# Tock.net
KiCad netlist of a schematic drawn in EAGLE
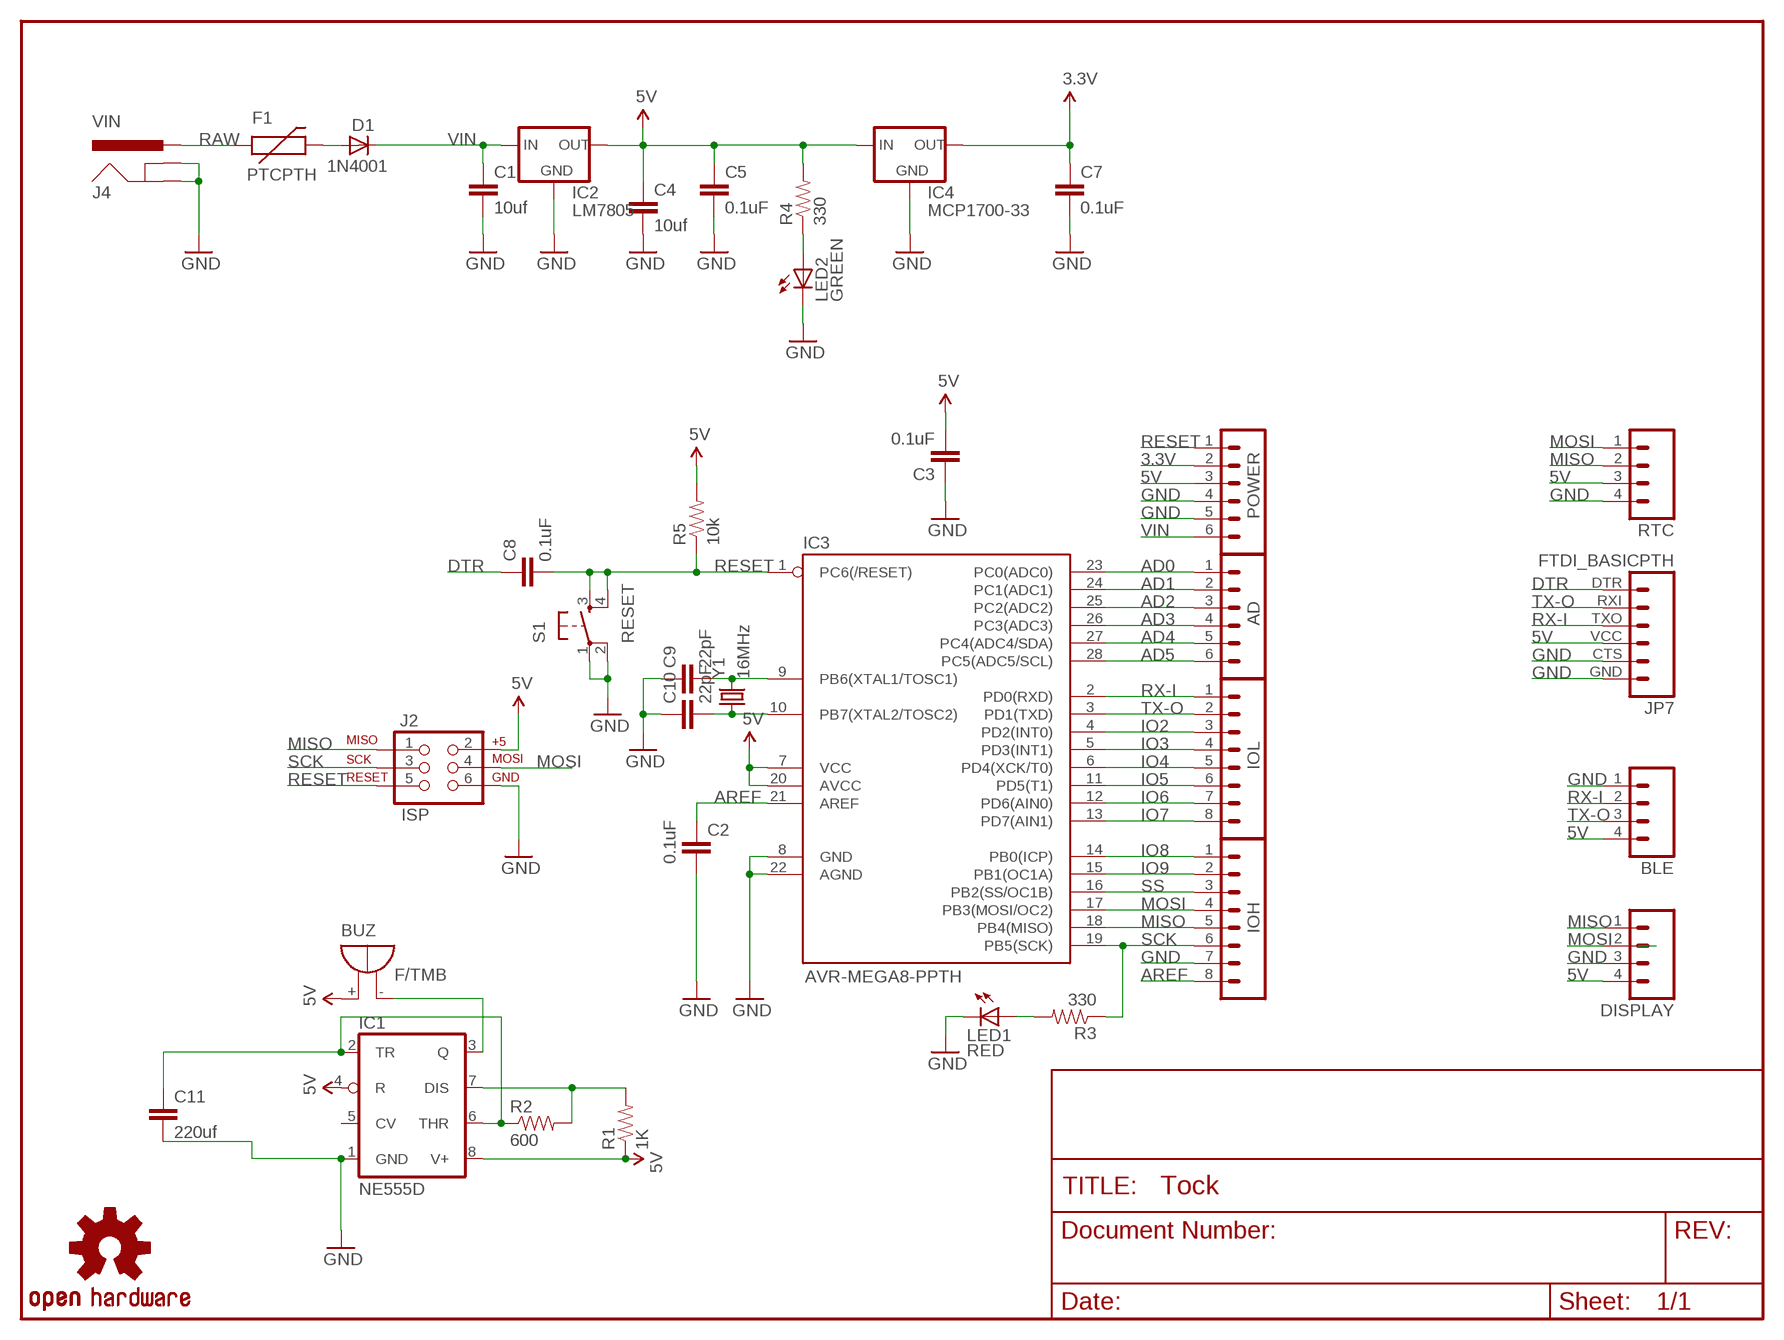
[diagram p0: schematic, sheet 1]

(export (version "E")
  (design (tool "Eeschema 10.0.6"))
  (components
    (comp (ref "AD")
      (value "M06LOCK")
      (footprint "eagle-import:1X06_LOCK")
      (libsource (lib "eagle-import") (part "M06LOCK"))
    )
    (comp (ref "BLE")
      (value "M04LOCK")
      (footprint "eagle-import:1X04_LOCK")
      (libsource (lib "eagle-import") (part "M04LOCK"))
    )
    (comp (ref "BUZ")
      (value "F/TMB")
      (footprint "eagle-import:F_TMB")
      (libsource (lib "eagle-import") (part "F/TMB"))
    )
    (comp (ref "C1")
      (value "10uf")
      (footprint "eagle-import:0805")
      (libsource (lib "eagle-import") (part "SparkFun-Passives_CAP0805"))
    )
    (comp (ref "C2")
      (value "0.1uF")
      (footprint "eagle-import:0805")
      (libsource (lib "eagle-import") (part "SparkFun-Passives_CAP0805"))
    )
    (comp (ref "C3")
      (value "0.1uF")
      (footprint "eagle-import:CAP-PTH-SMALL2")
      (libsource (lib "eagle-import") (part "CAPPTH2"))
    )
    (comp (ref "C4")
      (value "10uf")
      (footprint "eagle-import:0805")
      (libsource (lib "eagle-import") (part "SparkFun-Passives_CAP0805"))
    )
    (comp (ref "C5")
      (value "0.1uF")
      (footprint "eagle-import:0805")
      (libsource (lib "eagle-import") (part "SparkFun-Passives_CAP0805"))
    )
    (comp (ref "C7")
      (value "0.1uF")
      (footprint "eagle-import:0805")
      (libsource (lib "eagle-import") (part "SparkFun-Passives_CAP0805"))
    )
    (comp (ref "C8")
      (value "0.1uF")
      (footprint "eagle-import:0805")
      (libsource (lib "eagle-import") (part "SparkFun-Passives_CAP0805"))
    )
    (comp (ref "C9")
      (value "22pF")
      (footprint "eagle-import:0805")
      (libsource (lib "eagle-import") (part "SparkFun-Passives_CAP0805"))
    )
    (comp (ref "C10")
      (value "22pF")
      (footprint "eagle-import:0805")
      (libsource (lib "eagle-import") (part "SparkFun-Passives_CAP0805"))
    )
    (comp (ref "C11")
      (value "220uf")
      (footprint "eagle-import:0805")
      (libsource (lib "eagle-import") (part "SparkFun-Passives_CAP0805"))
    )
    (comp (ref "D1")
      (value "1N4001")
      (footprint "eagle-import:DIODE-1N4001")
      (libsource (lib "eagle-import") (part "DIODEPTH"))
    )
    (comp (ref "DISPLAY")
      (value "M04LOCK")
      (footprint "eagle-import:1X04_LOCK")
      (libsource (lib "eagle-import") (part "M04LOCK"))
    )
    (comp (ref "F1")
      (value "PTCPTH")
      (footprint "eagle-import:PTC")
      (libsource (lib "eagle-import") (part "PTCPTH"))
    )
    (comp (ref "IC1")
      (value "NE555D")
      (footprint "eagle-import:SO08")
      (libsource (lib "eagle-import") (part "555DNE"))
    )
    (comp (ref "IC2")
      (value "LM7805")
      (footprint "eagle-import:TO-220-ALT")
      (libsource (lib "eagle-import") (part "V_REG_78XX-TO-220"))
    )
    (comp (ref "IC3")
      (value "AVR-MEGA8-PPTH")
      (footprint "eagle-import:DIL28-3")
      (libsource (lib "eagle-import") (part "AVR-MEGA8-PPTH"))
    )
    (comp (ref "IC4")
      (value "MCP1700-33")
      (footprint "eagle-import:TO-92")
      (libsource (lib "eagle-import") (part "V_REG_78XXTO-92"))
    )
    (comp (ref "IOH")
      (value "M08LOCK")
      (footprint "eagle-import:1X08_LOCK")
      (libsource (lib "eagle-import") (part "M08LOCK"))
    )
    (comp (ref "IOL")
      (value "M08LOCK")
      (footprint "eagle-import:1X08_LOCK")
      (libsource (lib "eagle-import") (part "M08LOCK"))
    )
    (comp (ref "J2")
      (value "ISP")
      (footprint "eagle-import:2X3")
      (libsource (lib "eagle-import") (part "AVR_SPI_PRG_6PTH"))
    )
    (comp (ref "J4")
      (value "VIN")
      (footprint "eagle-import:POWER_JACK_PTH_LOCK")
      (libsource (lib "eagle-import") (part "POWER_JACKPTH_LOCK"))
    )
    (comp (ref "JP7")
      (value "FTDI_BASICPTH")
      (footprint "eagle-import:FTDI_BASIC")
      (libsource (lib "eagle-import") (part "FTDI_BASICPTH"))
    )
    (comp (ref "LED1")
      (value "RED")
      (footprint "eagle-import:CHIP-LED0805")
      (libsource (lib "eagle-import") (part "LEDCHIP-LED0805"))
    )
    (comp (ref "LED2")
      (value "GREEN")
      (footprint "eagle-import:CHIP-LED0805")
      (libsource (lib "eagle-import") (part "LEDCHIP-LED0805"))
    )
    (comp (ref "POWER")
      (value "M06LOCK")
      (footprint "eagle-import:1X06_LOCK")
      (libsource (lib "eagle-import") (part "M06LOCK"))
    )
    (comp (ref "R1")
      (value "1K")
      (footprint "eagle-import:0805")
      (libsource (lib "eagle-import") (part "RESISTOR0805-RES"))
    )
    (comp (ref "R2")
      (value "600")
      (footprint "eagle-import:0805")
      (libsource (lib "eagle-import") (part "RESISTOR0805-RES"))
    )
    (comp (ref "R3")
      (value "330")
      (footprint "eagle-import:0805")
      (libsource (lib "eagle-import") (part "RESISTOR0805-RES"))
    )
    (comp (ref "R4")
      (value "330")
      (footprint "eagle-import:0805")
      (libsource (lib "eagle-import") (part "RESISTOR0805-RES"))
    )
    (comp (ref "R5")
      (value "10k")
      (footprint "eagle-import:0805")
      (libsource (lib "eagle-import") (part "RESISTOR0805-RES"))
    )
    (comp (ref "RTC")
      (value "M04LOCK")
      (footprint "eagle-import:1X04_LOCK")
      (libsource (lib "eagle-import") (part "M04LOCK"))
    )
    (comp (ref "S1")
      (value "RESET")
      (footprint "eagle-import:TACTILE-PTH")
      (libsource (lib "eagle-import") (part "TAC_SWITCHPTH"))
    )
    (comp (ref "U$7")
      (value "OSHW-LOGOM")
      (footprint "eagle-import:OSHW-LOGO-M")
      (libsource (lib "eagle-import") (part "OSHW-LOGOM"))
    )
    (comp (ref "Y1")
      (value "16MHz")
      (footprint "eagle-import:HC49US")
      (libsource (lib "eagle-import") (part "CRYSTALHC49US"))
    )
  )
  (nets
    (net (code "1") (name "/AD0") (class "Default")
      (node (ref "AD") (pin "1") (pinfunction "1_1") (pintype "passive"))
      (node (ref "IC3") (pin "23") (pinfunction "PC0(ADC0)_23") (pintype "bidirectional"))
    )
    (net (code "2") (name "/AD1") (class "Default")
      (node (ref "AD") (pin "2") (pinfunction "2_2") (pintype "passive"))
      (node (ref "IC3") (pin "24") (pinfunction "PC1(ADC1)_24") (pintype "bidirectional"))
    )
    (net (code "3") (name "/AD2") (class "Default")
      (node (ref "AD") (pin "3") (pinfunction "3_3") (pintype "passive"))
      (node (ref "IC3") (pin "25") (pinfunction "PC2(ADC2)_25") (pintype "bidirectional"))
    )
    (net (code "4") (name "/AD3") (class "Default")
      (node (ref "AD") (pin "4") (pinfunction "4_4") (pintype "passive"))
      (node (ref "IC3") (pin "26") (pinfunction "PC3(ADC3)_26") (pintype "bidirectional"))
    )
    (net (code "5") (name "/AD4") (class "Default")
      (node (ref "AD") (pin "5") (pinfunction "5_5") (pintype "passive"))
      (node (ref "IC3") (pin "27") (pinfunction "PC4(ADC4/SDA)_27") (pintype "bidirectional"))
    )
    (net (code "6") (name "/AD5") (class "Default")
      (node (ref "AD") (pin "6") (pinfunction "6_6") (pintype "passive"))
      (node (ref "IC3") (pin "28") (pinfunction "PC5(ADC5/SCL)_28") (pintype "bidirectional"))
    )
    (net (code "7") (name "/AREF") (class "Default")
      (node (ref "C2") (pin "1") (pinfunction "1_1") (pintype "passive"))
      (node (ref "IC3") (pin "21") (pinfunction "AREF_21") (pintype "bidirectional"))
      (node (ref "IOH") (pin "8") (pinfunction "8_8") (pintype "passive"))
    )
    (net (code "8") (name "/DTR") (class "Default")
      (node (ref "C8") (pin "1") (pinfunction "1_1") (pintype "passive"))
      (node (ref "JP7") (pin "DTR") (pinfunction "1_DTR") (pintype "passive"))
    )
    (net (code "9") (name "/IO2") (class "Default")
      (node (ref "IC3") (pin "4") (pinfunction "PD2(INT0)_4") (pintype "bidirectional"))
      (node (ref "IOL") (pin "3") (pinfunction "3_3") (pintype "passive"))
    )
    (net (code "10") (name "/IO3") (class "Default")
      (node (ref "IC3") (pin "5") (pinfunction "PD3(INT1)_5") (pintype "bidirectional"))
      (node (ref "IOL") (pin "4") (pinfunction "4_4") (pintype "passive"))
    )
    (net (code "11") (name "/IO4") (class "Default")
      (node (ref "IC3") (pin "6") (pinfunction "PD4(XCK/T0)_6") (pintype "bidirectional"))
      (node (ref "IOL") (pin "5") (pinfunction "5_5") (pintype "passive"))
    )
    (net (code "12") (name "/IO5") (class "Default")
      (node (ref "IC3") (pin "11") (pinfunction "PD5(T1)_11") (pintype "bidirectional"))
      (node (ref "IOL") (pin "6") (pinfunction "6_6") (pintype "passive"))
    )
    (net (code "13") (name "/IO6") (class "Default")
      (node (ref "IC3") (pin "12") (pinfunction "PD6(AIN0)_12") (pintype "bidirectional"))
      (node (ref "IOL") (pin "7") (pinfunction "7_7") (pintype "passive"))
    )
    (net (code "14") (name "/IO7") (class "Default")
      (node (ref "IC3") (pin "13") (pinfunction "PD7(AIN1)_13") (pintype "bidirectional"))
      (node (ref "IOL") (pin "8") (pinfunction "8_8") (pintype "passive"))
    )
    (net (code "15") (name "/IO8") (class "Default")
      (node (ref "IC3") (pin "14") (pinfunction "PB0(ICP)_14") (pintype "bidirectional"))
      (node (ref "IOH") (pin "1") (pinfunction "1_1") (pintype "passive"))
    )
    (net (code "16") (name "/IO9") (class "Default")
      (node (ref "IC3") (pin "15") (pinfunction "PB1(OC1A)_15") (pintype "bidirectional"))
      (node (ref "IOH") (pin "2") (pinfunction "2_2") (pintype "passive"))
    )
    (net (code "17") (name "/MISO") (class "Default")
      (node (ref "DISPLAY") (pin "1") (pinfunction "1_1") (pintype "passive"))
      (node (ref "IC3") (pin "18") (pinfunction "PB4(MISO)_18") (pintype "bidirectional"))
      (node (ref "IOH") (pin "5") (pinfunction "5_5") (pintype "passive"))
      (node (ref "J2") (pin "1") (pinfunction "1_1") (pintype "passive"))
      (node (ref "RTC") (pin "2") (pinfunction "2_2") (pintype "passive"))
    )
    (net (code "18") (name "/MOSI") (class "Default")
      (node (ref "DISPLAY") (pin "2") (pinfunction "2_2") (pintype "passive"))
      (node (ref "IC3") (pin "17") (pinfunction "PB3(MOSI/OC2)_17") (pintype "bidirectional"))
      (node (ref "IOH") (pin "4") (pinfunction "4_4") (pintype "passive"))
      (node (ref "J2") (pin "4") (pinfunction "4_4") (pintype "passive"))
      (node (ref "RTC") (pin "1") (pinfunction "1_1") (pintype "passive"))
    )
    (net (code "19") (name "/RAW") (class "Default")
      (node (ref "F1") (pin "P$1") (pinfunction "1_P$1") (pintype "bidirectional"))
      (node (ref "J4") (pin "PWR") (pinfunction "PWR_PWR") (pintype "bidirectional"))
    )
    (net (code "20") (name "/RESET") (class "Default")
      (node (ref "C8") (pin "2") (pinfunction "2_2") (pintype "passive"))
      (node (ref "IC3") (pin "1") (pinfunction "PC6(/RESET)_1") (pintype "bidirectional"))
      (node (ref "J2") (pin "5") (pinfunction "5_5") (pintype "passive"))
      (node (ref "POWER") (pin "1") (pinfunction "1_1") (pintype "passive"))
      (node (ref "R5") (pin "1") (pinfunction "1_1") (pintype "passive"))
      (node (ref "S1") (pin "3") (pinfunction "3_3") (pintype "passive"))
      (node (ref "S1") (pin "4") (pinfunction "4_4") (pintype "passive"))
    )
    (net (code "21") (name "/RX-I") (class "Default")
      (node (ref "BLE") (pin "2") (pinfunction "2_2") (pintype "passive"))
      (node (ref "IC3") (pin "2") (pinfunction "PD0(RXD)_2") (pintype "bidirectional"))
      (node (ref "IOL") (pin "1") (pinfunction "1_1") (pintype "passive"))
      (node (ref "JP7") (pin "TXO") (pinfunction "3_TXO") (pintype "passive"))
    )
    (net (code "22") (name "/SCK") (class "Default")
      (node (ref "IC3") (pin "19") (pinfunction "PB5(SCK)_19") (pintype "bidirectional"))
      (node (ref "IOH") (pin "6") (pinfunction "6_6") (pintype "passive"))
      (node (ref "J2") (pin "3") (pinfunction "3_3") (pintype "passive"))
      (node (ref "R3") (pin "1") (pinfunction "1_1") (pintype "passive"))
    )
    (net (code "23") (name "/SS") (class "Default")
      (node (ref "IC3") (pin "16") (pinfunction "PB2(SS/OC1B)_16") (pintype "bidirectional"))
      (node (ref "IOH") (pin "3") (pinfunction "3_3") (pintype "passive"))
    )
    (net (code "24") (name "/TX-O") (class "Default")
      (node (ref "BLE") (pin "3") (pinfunction "3_3") (pintype "passive"))
      (node (ref "IC3") (pin "3") (pinfunction "PD1(TXD)_3") (pintype "bidirectional"))
      (node (ref "IOL") (pin "2") (pinfunction "2_2") (pintype "passive"))
      (node (ref "JP7") (pin "RXI") (pinfunction "2_RXI") (pintype "passive"))
    )
    (net (code "25") (name "/VIN") (class "Default")
      (node (ref "C1") (pin "1") (pinfunction "1_1") (pintype "passive"))
      (node (ref "D1") (pin "C") (pinfunction "C_C") (pintype "passive"))
      (node (ref "IC2") (pin "IN") (pinfunction "IN_IN") (pintype "input"))
      (node (ref "POWER") (pin "6") (pinfunction "6_6") (pintype "passive"))
    )
    (net (code "26") (name "3.3V") (class "Default")
      (node (ref "C7") (pin "1") (pinfunction "1_1") (pintype "passive"))
      (node (ref "IC4") (pin "3") (pinfunction "OUT_3") (pintype "output"))
      (node (ref "POWER") (pin "2") (pinfunction "2_2") (pintype "passive"))
    )
    (net (code "27") (name "5V") (class "Default")
      (node (ref "BLE") (pin "4") (pinfunction "4_4") (pintype "passive"))
      (node (ref "BUZ") (pin "+") (pinfunction "+_+") (pintype "passive"))
      (node (ref "C3") (pin "2") (pinfunction "2_2") (pintype "passive"))
      (node (ref "C4") (pin "1") (pinfunction "1_1") (pintype "passive"))
      (node (ref "C5") (pin "1") (pinfunction "1_1") (pintype "passive"))
      (node (ref "DISPLAY") (pin "4") (pinfunction "4_4") (pintype "passive"))
      (node (ref "IC1") (pin "4") (pinfunction "R_4") (pintype "input"))
      (node (ref "IC1") (pin "8") (pinfunction "V+_8") (pintype "power_in"))
      (node (ref "IC2") (pin "OUT") (pinfunction "OUT_OUT") (pintype "output"))
      (node (ref "IC3") (pin "20") (pinfunction "AVCC_20") (pintype "bidirectional"))
      (node (ref "IC3") (pin "7") (pinfunction "VCC_7") (pintype "bidirectional"))
      (node (ref "IC4") (pin "2") (pinfunction "IN_2") (pintype "input"))
      (node (ref "J2") (pin "2") (pinfunction "2_2") (pintype "passive"))
      (node (ref "JP7") (pin "VCC") (pinfunction "4_VCC") (pintype "passive"))
      (node (ref "POWER") (pin "3") (pinfunction "3_3") (pintype "passive"))
      (node (ref "R1") (pin "1") (pinfunction "1_1") (pintype "passive"))
      (node (ref "R4") (pin "2") (pinfunction "2_2") (pintype "passive"))
      (node (ref "R5") (pin "2") (pinfunction "2_2") (pintype "passive"))
      (node (ref "RTC") (pin "3") (pinfunction "3_3") (pintype "passive"))
    )
    (net (code "28") (name "GND") (class "Default")
      (node (ref "BLE") (pin "1") (pinfunction "1_1") (pintype "passive"))
      (node (ref "C1") (pin "2") (pinfunction "2_2") (pintype "passive"))
      (node (ref "C10") (pin "1") (pinfunction "1_1") (pintype "passive"))
      (node (ref "C11") (pin "2") (pinfunction "2_2") (pintype "passive"))
      (node (ref "C2") (pin "2") (pinfunction "2_2") (pintype "passive"))
      (node (ref "C3") (pin "1") (pinfunction "1_1") (pintype "passive"))
      (node (ref "C4") (pin "2") (pinfunction "2_2") (pintype "passive"))
      (node (ref "C5") (pin "2") (pinfunction "2_2") (pintype "passive"))
      (node (ref "C7") (pin "2") (pinfunction "2_2") (pintype "passive"))
      (node (ref "C9") (pin "1") (pinfunction "1_1") (pintype "passive"))
      (node (ref "DISPLAY") (pin "3") (pinfunction "3_3") (pintype "passive"))
      (node (ref "IC1") (pin "1") (pinfunction "GND_1") (pintype "power_in"))
      (node (ref "IC2") (pin "GND") (pinfunction "GND_GND") (pintype "input"))
      (node (ref "IC3") (pin "22") (pinfunction "AGND_22") (pintype "bidirectional"))
      (node (ref "IC3") (pin "8") (pinfunction "GND_8") (pintype "bidirectional"))
      (node (ref "IC4") (pin "1") (pinfunction "GND_1") (pintype "input"))
      (node (ref "IOH") (pin "7") (pinfunction "7_7") (pintype "passive"))
      (node (ref "J2") (pin "6") (pinfunction "6_6") (pintype "passive"))
      (node (ref "J4") (pin "GND") (pinfunction "GND_GND") (pintype "bidirectional"))
      (node (ref "J4") (pin "GNDBREAK") (pinfunction "GNDBREAK_GNDBREAK") (pintype "bidirectional"))
      (node (ref "JP7") (pin "CTS") (pinfunction "5_CTS") (pintype "passive"))
      (node (ref "JP7") (pin "GND") (pinfunction "6_GND") (pintype "passive"))
      (node (ref "LED1") (pin "C") (pinfunction "C_C") (pintype "passive"))
      (node (ref "LED2") (pin "C") (pinfunction "C_C") (pintype "passive"))
      (node (ref "POWER") (pin "4") (pinfunction "4_4") (pintype "passive"))
      (node (ref "POWER") (pin "5") (pinfunction "5_5") (pintype "passive"))
      (node (ref "RTC") (pin "4") (pinfunction "4_4") (pintype "passive"))
      (node (ref "S1") (pin "1") (pinfunction "1_1") (pintype "passive"))
      (node (ref "S1") (pin "2") (pinfunction "2_2") (pintype "passive"))
    )
    (net (code "29") (name "Net-(F1-2)") (class "Default")
      (node (ref "D1") (pin "A") (pinfunction "A_A") (pintype "passive"))
      (node (ref "F1") (pin "P$2") (pinfunction "2_P$2") (pintype "bidirectional"))
    )
    (net (code "30") (name "Net-(IC1-DIS)") (class "Default")
      (node (ref "IC1") (pin "7") (pinfunction "DIS_7") (pintype "input"))
      (node (ref "R1") (pin "2") (pinfunction "2_2") (pintype "passive"))
      (node (ref "R2") (pin "2") (pinfunction "2_2") (pintype "passive"))
    )
    (net (code "31") (name "Net-(IC1-Q)") (class "Default")
      (node (ref "BUZ") (pin "-") (pinfunction "-_-") (pintype "passive"))
      (node (ref "IC1") (pin "3") (pinfunction "Q_3") (pintype "output"))
    )
    (net (code "32") (name "Net-(IC1-THR)") (class "Default")
      (node (ref "C11") (pin "1") (pinfunction "1_1") (pintype "passive"))
      (node (ref "IC1") (pin "2") (pinfunction "TR_2") (pintype "input"))
      (node (ref "IC1") (pin "6") (pinfunction "THR_6") (pintype "input"))
      (node (ref "R2") (pin "1") (pinfunction "1_1") (pintype "passive"))
    )
    (net (code "33") (name "Net-(IC3-PB6(XTAL1{slash}TOSC1))") (class "Default")
      (node (ref "C9") (pin "2") (pinfunction "2_2") (pintype "passive"))
      (node (ref "IC3") (pin "9") (pinfunction "PB6(XTAL1/TOSC1)_9") (pintype "bidirectional"))
      (node (ref "Y1") (pin "2") (pinfunction "2_2") (pintype "passive"))
    )
    (net (code "34") (name "Net-(IC3-PB7(XTAL2{slash}TOSC2))") (class "Default")
      (node (ref "C10") (pin "2") (pinfunction "2_2") (pintype "passive"))
      (node (ref "IC3") (pin "10") (pinfunction "PB7(XTAL2/TOSC2)_10") (pintype "bidirectional"))
      (node (ref "Y1") (pin "1") (pinfunction "1_1") (pintype "passive"))
    )
    (net (code "35") (name "Net-(LED1-PadA)") (class "Default")
      (node (ref "LED1") (pin "A") (pinfunction "A_A") (pintype "passive"))
      (node (ref "R3") (pin "2") (pinfunction "2_2") (pintype "passive"))
    )
    (net (code "36") (name "Net-(LED2-PadA)") (class "Default")
      (node (ref "LED2") (pin "A") (pinfunction "A_A") (pintype "passive"))
      (node (ref "R4") (pin "1") (pinfunction "1_1") (pintype "passive"))
    )
    (net (code "37") (name "unconnected-(IC1-CV-Pad5)") (class "Default")
      (node (ref "IC1") (pin "5") (pinfunction "CV_5") (pintype "input"))
    )
  )
)
